# PCB_3U_RJ45.net
KiCad netlist of a schematic drawn in Altium Designer
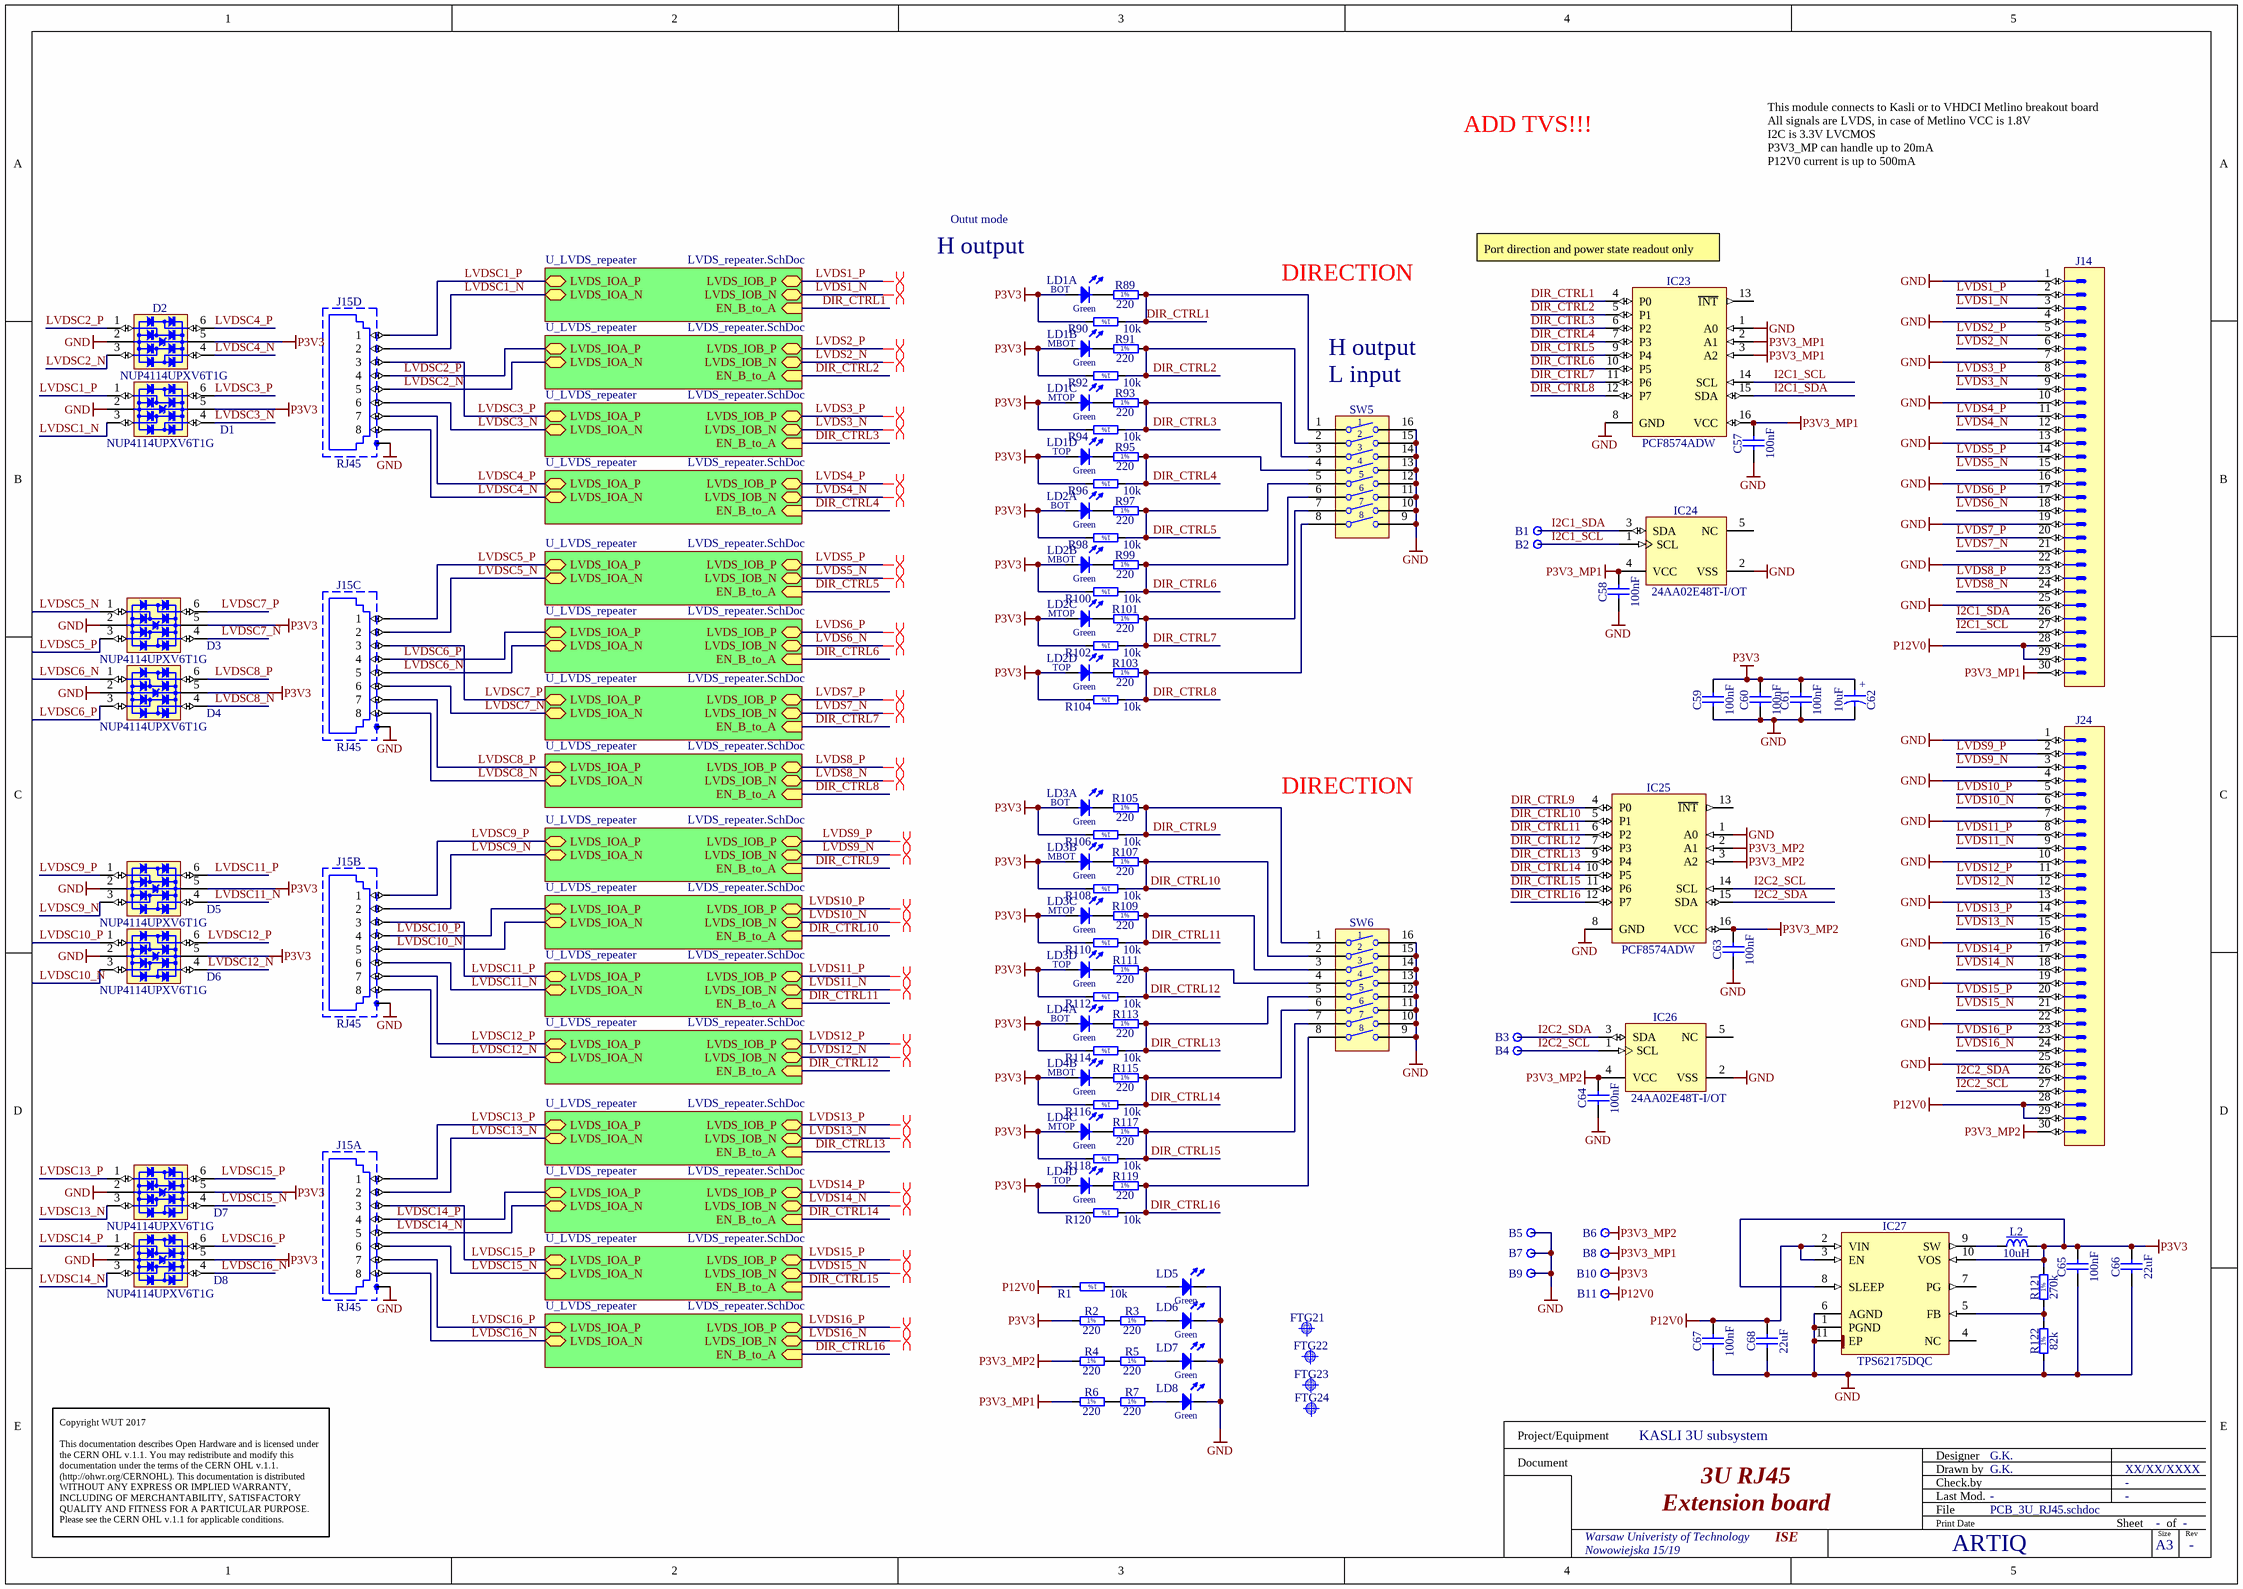
[diagram p0: PCB_3U_RJ45.schdoc]

(export (version "E")
  (design (tool "Eeschema 10.0.6"))
  (components
    (comp (ref "B1")
      (value "Plated Hole")
      (footprint "c130h60")
      (description "Single Terminal Socket")
      (fields (field (name "PART NUMBER") "PLATED_HOLE0.6_PAD1.3") (field (name "AUTHOR") "CERN DEM MR"))
      (libsource (lib "Eletro-mechanical") (part "Single Terminal Socket"))
    )
    (comp (ref "B2")
      (value "Plated Hole")
      (footprint "c130h60")
      (description "Single Terminal Socket")
      (fields (field (name "PART NUMBER") "PLATED_HOLE0.6_PAD1.3") (field (name "AUTHOR") "CERN DEM MR"))
      (libsource (lib "Eletro-mechanical") (part "Single Terminal Socket"))
    )
    (comp (ref "B3")
      (value "Plated Hole")
      (footprint "c130h60")
      (description "Single Terminal Socket")
      (fields (field (name "PART NUMBER") "PLATED_HOLE0.6_PAD1.3") (field (name "AUTHOR") "CERN DEM MR"))
      (libsource (lib "Eletro-mechanical") (part "Single Terminal Socket"))
    )
    (comp (ref "B4")
      (value "Plated Hole")
      (footprint "c130h60")
      (description "Single Terminal Socket")
      (fields (field (name "PART NUMBER") "PLATED_HOLE0.6_PAD1.3") (field (name "AUTHOR") "CERN DEM MR"))
      (libsource (lib "Eletro-mechanical") (part "Single Terminal Socket"))
    )
    (comp (ref "B5")
      (value "Plated Hole")
      (footprint "c130h60")
      (description "Single Terminal Socket")
      (fields (field (name "PART NUMBER") "PLATED_HOLE0.6_PAD1.3") (field (name "AUTHOR") "CERN DEM MR"))
      (libsource (lib "Eletro-mechanical") (part "Single Terminal Socket"))
    )
    (comp (ref "B6")
      (value "Plated Hole")
      (footprint "c130h60")
      (description "Single Terminal Socket")
      (fields (field (name "PART NUMBER") "PLATED_HOLE0.6_PAD1.3") (field (name "AUTHOR") "CERN DEM MR"))
      (libsource (lib "Eletro-mechanical") (part "Single Terminal Socket"))
    )
    (comp (ref "B7")
      (value "Plated Hole")
      (footprint "c130h60")
      (description "Single Terminal Socket")
      (fields (field (name "PART NUMBER") "PLATED_HOLE0.6_PAD1.3") (field (name "AUTHOR") "CERN DEM MR"))
      (libsource (lib "Eletro-mechanical") (part "Single Terminal Socket"))
    )
    (comp (ref "B8")
      (value "Plated Hole")
      (footprint "c130h60")
      (description "Single Terminal Socket")
      (fields (field (name "PART NUMBER") "PLATED_HOLE0.6_PAD1.3") (field (name "AUTHOR") "CERN DEM MR"))
      (libsource (lib "Eletro-mechanical") (part "Single Terminal Socket"))
    )
    (comp (ref "B9")
      (value "Plated Hole")
      (footprint "c130h60")
      (description "Single Terminal Socket")
      (fields (field (name "PART NUMBER") "PLATED_HOLE0.6_PAD1.3") (field (name "AUTHOR") "CERN DEM MR"))
      (libsource (lib "Eletro-mechanical") (part "Single Terminal Socket"))
    )
    (comp (ref "B10")
      (value "Plated Hole")
      (footprint "c130h60")
      (description "Single Terminal Socket")
      (fields (field (name "PART NUMBER") "PLATED_HOLE0.6_PAD1.3") (field (name "AUTHOR") "CERN DEM MR"))
      (libsource (lib "Eletro-mechanical") (part "Single Terminal Socket"))
    )
    (comp (ref "B11")
      (value "Plated Hole")
      (footprint "c130h60")
      (description "Single Terminal Socket")
      (fields (field (name "PART NUMBER") "PLATED_HOLE0.6_PAD1.3") (field (name "AUTHOR") "CERN DEM MR"))
      (libsource (lib "Eletro-mechanical") (part "Single Terminal Socket"))
    )
    (comp (ref "C57")
      (value "100nF")
      (footprint "CAPC1005X55N")
      (description "Non-polarised capacitor")
      (fields
        (field (name "PART NUMBER") "CC0402_100NF_16V_10%_X5R")
        (field (name "VOLTAGE") "16V")
        (field (name "AUTHOR") "CERN DEM JLC")
      )
      (libsource (lib "Capacitors") (part "Capacitor - non polarized"))
    )
    (comp (ref "C58")
      (value "100nF")
      (footprint "CAPC1005X55N")
      (description "Non-polarised capacitor")
      (fields
        (field (name "PART NUMBER") "CC0402_100NF_16V_10%_X5R")
        (field (name "VOLTAGE") "16V")
        (field (name "AUTHOR") "CERN DEM JLC")
      )
      (libsource (lib "Capacitors") (part "Capacitor - non polarized"))
    )
    (comp (ref "C59")
      (value "100nF")
      (footprint "CAPC1005X55N")
      (description "Non-polarised capacitor")
      (fields
        (field (name "PART NUMBER") "CC0402_100NF_16V_10%_X5R")
        (field (name "VOLTAGE") "16V")
        (field (name "AUTHOR") "CERN DEM JLC")
      )
      (libsource (lib "Capacitors") (part "Capacitor - non polarized"))
    )
    (comp (ref "C60")
      (value "100nF")
      (footprint "CAPC1005X55N")
      (description "Non-polarised capacitor")
      (fields
        (field (name "PART NUMBER") "CC0402_100NF_16V_10%_X5R")
        (field (name "VOLTAGE") "16V")
        (field (name "AUTHOR") "CERN DEM JLC")
      )
      (libsource (lib "Capacitors") (part "Capacitor - non polarized"))
    )
    (comp (ref "C61")
      (value "100nF")
      (footprint "CAPC1005X55N")
      (description "Non-polarised capacitor")
      (fields
        (field (name "PART NUMBER") "CC0402_100NF_16V_10%_X5R")
        (field (name "VOLTAGE") "16V")
        (field (name "AUTHOR") "CERN DEM JLC")
      )
      (libsource (lib "Capacitors") (part "Capacitor - non polarized"))
    )
    (comp (ref "C62")
      (value "10uF")
      (footprint "CAPAE430X540N")
      (description "Polarised capacitor")
      (fields
        (field (name "PART NUMBER") "CAE430-540_10UF_16V_20%")
        (field (name "VOLTAGE") "16V")
        (field (name "AUTHOR") "CERN DEM JLC")
      )
      (libsource (lib "Capacitors") (part "Capacitor - polarized"))
    )
    (comp (ref "C63")
      (value "100nF")
      (footprint "CAPC1005X55N")
      (description "Non-polarised capacitor")
      (fields
        (field (name "PART NUMBER") "CC0402_100NF_16V_10%_X5R")
        (field (name "VOLTAGE") "16V")
        (field (name "AUTHOR") "CERN DEM JLC")
      )
      (libsource (lib "Capacitors") (part "Capacitor - non polarized"))
    )
    (comp (ref "C64")
      (value "100nF")
      (footprint "CAPC1005X55N")
      (description "Non-polarised capacitor")
      (fields
        (field (name "PART NUMBER") "CC0402_100NF_16V_10%_X5R")
        (field (name "VOLTAGE") "16V")
        (field (name "AUTHOR") "CERN DEM JLC")
      )
      (libsource (lib "Capacitors") (part "Capacitor - non polarized"))
    )
    (comp (ref "C65")
      (value "100nF")
      (footprint "CAPC1005X55N")
      (description "Non-polarised capacitor")
      (fields
        (field (name "PART NUMBER") "CC0402_100NF_16V_10%_X5R")
        (field (name "VOLTAGE") "16V")
        (field (name "AUTHOR") "CERN DEM JLC")
      )
      (libsource (lib "Capacitors") (part "Capacitor - non polarized"))
    )
    (comp (ref "C66")
      (value "22uF")
      (footprint "CAPC2012X135N")
      (description "Non-polarised capacitor")
      (fields
        (field (name "PART NUMBER") "CC0805_22UF_16V_10%_X5R")
        (field (name "VOLTAGE") "16V")
        (field (name "AUTHOR") "CERN DEM JLC")
      )
      (libsource (lib "Capacitors") (part "Capacitor - non polarized"))
    )
    (comp (ref "C67")
      (value "100nF")
      (footprint "CAPC1005X55N")
      (description "Non-polarised capacitor")
      (fields
        (field (name "PART NUMBER") "CC0402_100NF_16V_10%_X5R")
        (field (name "VOLTAGE") "16V")
        (field (name "AUTHOR") "CERN DEM JLC")
      )
      (libsource (lib "Capacitors") (part "Capacitor - non polarized"))
    )
    (comp (ref "C68")
      (value "22uF")
      (footprint "CAPC2012X135N")
      (description "Non-polarised capacitor")
      (fields
        (field (name "PART NUMBER") "CC0805_22UF_16V_10%_X5R")
        (field (name "VOLTAGE") "16V")
        (field (name "AUTHOR") "CERN DEM JLC")
      )
      (libsource (lib "Capacitors") (part "Capacitor - non polarized"))
    )
    (comp (ref "D1")
      (value "NUP4114UPXV6T1G")
      (footprint "SOTFL50P160X60-6N")
      (fields
        (field (name "VOLTAGE") "5.5V")
        (field (name "MANUFACTURER") "ON SEMICONDUCTOR")
        (field (name "AUTHOR") "CERN DEM JLC")
      )
      (libsource (lib "ICs And Semiconductors") (part "NUP4114"))
    )
    (comp (ref "D2")
      (value "NUP4114UPXV6T1G")
      (footprint "SOTFL50P160X60-6N")
      (fields
        (field (name "VOLTAGE") "5.5V")
        (field (name "MANUFACTURER") "ON SEMICONDUCTOR")
        (field (name "AUTHOR") "CERN DEM JLC")
      )
      (libsource (lib "ICs And Semiconductors") (part "NUP4114"))
    )
    (comp (ref "D3")
      (value "NUP4114UPXV6T1G")
      (footprint "SOTFL50P160X60-6N")
      (fields
        (field (name "VOLTAGE") "5.5V")
        (field (name "MANUFACTURER") "ON SEMICONDUCTOR")
        (field (name "AUTHOR") "CERN DEM JLC")
      )
      (libsource (lib "ICs And Semiconductors") (part "NUP4114"))
    )
    (comp (ref "D4")
      (value "NUP4114UPXV6T1G")
      (footprint "SOTFL50P160X60-6N")
      (fields
        (field (name "VOLTAGE") "5.5V")
        (field (name "MANUFACTURER") "ON SEMICONDUCTOR")
        (field (name "AUTHOR") "CERN DEM JLC")
      )
      (libsource (lib "ICs And Semiconductors") (part "NUP4114"))
    )
    (comp (ref "D5")
      (value "NUP4114UPXV6T1G")
      (footprint "SOTFL50P160X60-6N")
      (fields
        (field (name "VOLTAGE") "5.5V")
        (field (name "MANUFACTURER") "ON SEMICONDUCTOR")
        (field (name "AUTHOR") "CERN DEM JLC")
      )
      (libsource (lib "ICs And Semiconductors") (part "NUP4114"))
    )
    (comp (ref "D6")
      (value "NUP4114UPXV6T1G")
      (footprint "SOTFL50P160X60-6N")
      (fields
        (field (name "VOLTAGE") "5.5V")
        (field (name "MANUFACTURER") "ON SEMICONDUCTOR")
        (field (name "AUTHOR") "CERN DEM JLC")
      )
      (libsource (lib "ICs And Semiconductors") (part "NUP4114"))
    )
    (comp (ref "D7")
      (value "NUP4114UPXV6T1G")
      (footprint "SOTFL50P160X60-6N")
      (fields
        (field (name "VOLTAGE") "5.5V")
        (field (name "MANUFACTURER") "ON SEMICONDUCTOR")
        (field (name "AUTHOR") "CERN DEM JLC")
      )
      (libsource (lib "ICs And Semiconductors") (part "NUP4114"))
    )
    (comp (ref "D8")
      (value "NUP4114UPXV6T1G")
      (footprint "SOTFL50P160X60-6N")
      (fields
        (field (name "VOLTAGE") "5.5V")
        (field (name "MANUFACTURER") "ON SEMICONDUCTOR")
        (field (name "AUTHOR") "CERN DEM JLC")
      )
      (libsource (lib "ICs And Semiconductors") (part "NUP4114"))
    )
    (comp (ref "FTG21")
      (value "Use only in PCB")
      (footprint "FIDUCIAL_TOP_C100-200")
      (description "Fiducial Target")
      (fields (field (name "PART NUMBER") "FIDUCIAL_TARGET_C100-200") (field (name "AUTHOR") "CERN DEM JLC"))
      (libsource (lib "Eletro-mechanical") (part "Fiducial Target"))
    )
    (comp (ref "FTG22")
      (value "Use only in PCB")
      (footprint "FIDUCIAL_TOP_S100-200")
      (description "Fiducial Target")
      (fields (field (name "PART NUMBER") "FIDUCIAL_TARGET_S100-200") (field (name "AUTHOR") "CERN DEM JLC"))
      (libsource (lib "Eletro-mechanical") (part "Fiducial Target"))
    )
    (comp (ref "FTG23")
      (value "Use only in PCB")
      (footprint "FIDUCIAL_TOP_S200-400")
      (description "Fiducial Target")
      (fields (field (name "PART NUMBER") "FIDUCIAL_TARGET_S200-400") (field (name "AUTHOR") "CERN DEM JLC"))
      (libsource (lib "Eletro-mechanical") (part "Fiducial Target"))
    )
    (comp (ref "FTG24")
      (value "Use only in PCB")
      (footprint "FIDUCIAL_TOP_S100-200")
      (description "Fiducial Target")
      (fields (field (name "PART NUMBER") "FIDUCIAL_TARGET_S100-200") (field (name "AUTHOR") "CERN DEM JLC"))
      (libsource (lib "Eletro-mechanical") (part "Fiducial Target"))
    )
    (comp (ref "IC23")
      (value "PCF8574ADW")
      (footprint "SOIC127P1030X265-16N")
      (description "Remote 8-bit I/O Expander For I2C Bus")
      (fields (field (name "MANUFACTURER") "TEXAS INSTRUMENTS") (field (name "AUTHOR") "CERN DEM JLC"))
      (libsource (lib "ICs And Semiconductors") (part "PCF8574ADW"))
    )
    (comp (ref "IC24")
      (value "24AA02E48T-I/OT")
      (footprint "SOT95P280X145-5N")
      (description "1.7V-5.5V, 2K I2C Serial EEPROM With EUI-48 Node Identity")
      (fields (field (name "MANUFACTURER") "MICROCHIP TECHNOLOGY") (field (name "AUTHOR") "CERN DEM MR"))
      (libsource (lib "ICs And Semiconductors") (part "24AA02E48T-I/OT"))
    )
    (comp (ref "IC25")
      (value "PCF8574ADW")
      (footprint "SOIC127P1030X265-16N")
      (description "Remote 8-bit I/O Expander For I2C Bus")
      (fields (field (name "MANUFACTURER") "TEXAS INSTRUMENTS") (field (name "AUTHOR") "CERN DEM JLC"))
      (libsource (lib "ICs And Semiconductors") (part "PCF8574ADW"))
    )
    (comp (ref "IC26")
      (value "24AA02E48T-I/OT")
      (footprint "SOT95P280X145-5N")
      (description "1.7V-5.5V, 2K I2C Serial EEPROM With EUI-48 Node Identity")
      (fields (field (name "MANUFACTURER") "MICROCHIP TECHNOLOGY") (field (name "AUTHOR") "CERN DEM MR"))
      (libsource (lib "ICs And Semiconductors") (part "24AA02E48T-I/OT"))
    )
    (comp (ref "IC27")
      (value "TPS62175DQC")
      (footprint "SON50P200X300X80-11N-R94X250")
      (description "4.75-28VDC to 1-6VDC, 500mA Step-Down Converter With Sleep Mode")
      (fields (field (name "MANUFACTURER") "TEXAS INSTRUMENTS") (field (name "AUTHOR") "CERN DEM JMW"))
      (libsource (lib "ICs And Semiconductors") (part "TPS62175"))
    )
    (comp (ref "J14")
      (value "~")
      (footprint "3M_N2530-6002RB")
      (description "Connector 30 Male")
      (fields
        (field (name "PART NUMBER") "3M_N2530-6002RB")
        (field (name "MANUFACTURER") "3M")
        (field (name "AUTHOR") "CERN DEM JLC")
      )
      (libsource (lib "Connectors") (part "Connector 30 Male"))
    )
    (comp (ref "J15")
      (value "RJ45")
      (footprint "TYCO_5406203-3")
      (description "Connector 4 x RJ45 + Shield")
      (fields
        (field (name "PART NUMBER") "TYCO_5406203-3")
        (field (name "MANUFACTURER") "TYCO ELECTRONICS")
        (field (name "AUTHOR") "CERN DEM JLC")
      )
      (libsource (lib "Connectors") (part "Connector 4 x RJ45 + Shield"))
    )
    (comp (ref "J24")
      (value "~")
      (footprint "3M_N2530-6002RB")
      (description "Connector 30 Male")
      (fields
        (field (name "PART NUMBER") "3M_N2530-6002RB")
        (field (name "MANUFACTURER") "3M")
        (field (name "AUTHOR") "CERN DEM JLC")
      )
      (libsource (lib "Connectors") (part "Connector 30 Male"))
    )
    (comp (ref "L2")
      (value "10uH")
      (footprint "IND_MURATA-PS_8400")
      (description "Inductor With Core")
      (fields
        (field (name "PART NUMBER") "IND_10UH_10%_MURATA-PS_8400")
        (field (name "POWER") "950mA")
        (field (name "AUTHOR") "CERN DEM JLC")
      )
      (libsource (lib "Inductors & Transformers") (part "Inductor With Magnetic core"))
    )
    (comp (ref "LD1")
      (value "Green")
      (footprint "LED_BIVAR_H485CGDL")
      (description "LED x4 Green 1C2A-BOT_3C4A_5C6A_7C8A-TOP")
      (fields
        (field (name "PART NUMBER") "LED_BIVAR_H485CGDL")
        (field (name "MANUFACTURER") "BIVAR")
        (field (name "AUTHOR") "CERN DEM JLC")
      )
      (libsource (lib "ICs And Semiconductors") (part "LED x4 Green 1C2A-BOT_3C4A_5C6A_7C8A-TOP"))
    )
    (comp (ref "LD2")
      (value "Green")
      (footprint "LED_BIVAR_H485CGDL")
      (description "LED x4 Green 1C2A-BOT_3C4A_5C6A_7C8A-TOP")
      (fields
        (field (name "PART NUMBER") "LED_BIVAR_H485CGDL")
        (field (name "MANUFACTURER") "BIVAR")
        (field (name "AUTHOR") "CERN DEM JLC")
      )
      (libsource (lib "ICs And Semiconductors") (part "LED x4 Green 1C2A-BOT_3C4A_5C6A_7C8A-TOP"))
    )
    (comp (ref "LD3")
      (value "Green")
      (footprint "LED_BIVAR_H485CGDL")
      (description "LED x4 Green 1C2A-BOT_3C4A_5C6A_7C8A-TOP")
      (fields
        (field (name "PART NUMBER") "LED_BIVAR_H485CGDL")
        (field (name "MANUFACTURER") "BIVAR")
        (field (name "AUTHOR") "CERN DEM JLC")
      )
      (libsource (lib "ICs And Semiconductors") (part "LED x4 Green 1C2A-BOT_3C4A_5C6A_7C8A-TOP"))
    )
    (comp (ref "LD4")
      (value "Green")
      (footprint "LED_BIVAR_H485CGDL")
      (description "LED x4 Green 1C2A-BOT_3C4A_5C6A_7C8A-TOP")
      (fields
        (field (name "PART NUMBER") "LED_BIVAR_H485CGDL")
        (field (name "MANUFACTURER") "BIVAR")
        (field (name "AUTHOR") "CERN DEM JLC")
      )
      (libsource (lib "ICs And Semiconductors") (part "LED x4 Green 1C2A-BOT_3C4A_5C6A_7C8A-TOP"))
    )
    (comp (ref "LD5")
      (value "Green")
      (footprint "LED_KINGBRIGHT_KPH-1608CGCK")
      (description "LED Green 1C 2A")
      (fields
        (field (name "PART NUMBER") "LED_KINGBRIGHT_KPH-1608CGCK")
        (field (name "MANUFACTURER") "KINGBRIGHT")
        (field (name "AUTHOR") "CERN DEM JLC")
      )
      (libsource (lib "ICs And Semiconductors") (part "LED Green 1C 2A"))
    )
    (comp (ref "LD6")
      (value "Green")
      (footprint "LED_KINGBRIGHT_KPH-1608CGCK")
      (description "LED Green 1C 2A")
      (fields
        (field (name "PART NUMBER") "LED_KINGBRIGHT_KPH-1608CGCK")
        (field (name "MANUFACTURER") "KINGBRIGHT")
        (field (name "AUTHOR") "CERN DEM JLC")
      )
      (libsource (lib "ICs And Semiconductors") (part "LED Green 1C 2A"))
    )
    (comp (ref "LD7")
      (value "Green")
      (footprint "LED_KINGBRIGHT_KPH-1608CGCK")
      (description "LED Green 1C 2A")
      (fields
        (field (name "PART NUMBER") "LED_KINGBRIGHT_KPH-1608CGCK")
        (field (name "MANUFACTURER") "KINGBRIGHT")
        (field (name "AUTHOR") "CERN DEM JLC")
      )
      (libsource (lib "ICs And Semiconductors") (part "LED Green 1C 2A"))
    )
    (comp (ref "LD8")
      (value "Green")
      (footprint "LED_KINGBRIGHT_KPH-1608CGCK")
      (description "LED Green 1C 2A")
      (fields
        (field (name "PART NUMBER") "LED_KINGBRIGHT_KPH-1608CGCK")
        (field (name "MANUFACTURER") "KINGBRIGHT")
        (field (name "AUTHOR") "CERN DEM JLC")
      )
      (libsource (lib "ICs And Semiconductors") (part "LED Green 1C 2A"))
    )
    (comp (ref "R1")
      (value "10k")
      (footprint "RESC1005X40N")
      (description "Resistor - 1%")
      (fields
        (field (name "PART NUMBER") "R0402_10K_1%_0.0625W_100PPM")
        (field (name "POWER") "0.0625W")
        (field (name "AUTHOR") "CERN DEM JLC")
      )
      (libsource (lib "Resistors") (part "Resistor - 1%"))
    )
    (comp (ref "R2")
      (value "220")
      (footprint "RESC1608X55N")
      (description "Resistor - 1%")
      (fields
        (field (name "PART NUMBER") "R0603_220R_1%_0.1W_100PPM")
        (field (name "POWER") "0.1W")
        (field (name "AUTHOR") "CERN DEM JLC")
      )
      (libsource (lib "Resistors") (part "Resistor - 1%"))
    )
    (comp (ref "R3")
      (value "220")
      (footprint "RESC1608X55N")
      (description "Resistor - 1%")
      (fields
        (field (name "PART NUMBER") "R0603_220R_1%_0.1W_100PPM")
        (field (name "POWER") "0.1W")
        (field (name "AUTHOR") "CERN DEM JLC")
      )
      (libsource (lib "Resistors") (part "Resistor - 1%"))
    )
    (comp (ref "R4")
      (value "220")
      (footprint "RESC1608X55N")
      (description "Resistor - 1%")
      (fields
        (field (name "PART NUMBER") "R0603_220R_1%_0.1W_100PPM")
        (field (name "POWER") "0.1W")
        (field (name "AUTHOR") "CERN DEM JLC")
      )
      (libsource (lib "Resistors") (part "Resistor - 1%"))
    )
    (comp (ref "R5")
      (value "220")
      (footprint "RESC1608X55N")
      (description "Resistor - 1%")
      (fields
        (field (name "PART NUMBER") "R0603_220R_1%_0.1W_100PPM")
        (field (name "POWER") "0.1W")
        (field (name "AUTHOR") "CERN DEM JLC")
      )
      (libsource (lib "Resistors") (part "Resistor - 1%"))
    )
    (comp (ref "R6")
      (value "220")
      (footprint "RESC1608X55N")
      (description "Resistor - 1%")
      (fields
        (field (name "PART NUMBER") "R0603_220R_1%_0.1W_100PPM")
        (field (name "POWER") "0.1W")
        (field (name "AUTHOR") "CERN DEM JLC")
      )
      (libsource (lib "Resistors") (part "Resistor - 1%"))
    )
    (comp (ref "R7")
      (value "220")
      (footprint "RESC1608X55N")
      (description "Resistor - 1%")
      (fields
        (field (name "PART NUMBER") "R0603_220R_1%_0.1W_100PPM")
        (field (name "POWER") "0.1W")
        (field (name "AUTHOR") "CERN DEM JLC")
      )
      (libsource (lib "Resistors") (part "Resistor - 1%"))
    )
    (comp (ref "R89")
      (value "220")
      (footprint "RESC1608X55N")
      (description "Resistor - 1%")
      (fields
        (field (name "PART NUMBER") "R0603_220R_1%_0.1W_100PPM")
        (field (name "POWER") "0.1W")
        (field (name "AUTHOR") "CERN DEM JLC")
      )
      (libsource (lib "Resistors") (part "Resistor - 1%"))
    )
    (comp (ref "R90")
      (value "10k")
      (footprint "RESC1005X40N")
      (description "Resistor - 1%")
      (fields
        (field (name "PART NUMBER") "R0402_10K_1%_0.0625W_100PPM")
        (field (name "POWER") "0.0625W")
        (field (name "AUTHOR") "CERN DEM JLC")
      )
      (libsource (lib "Resistors") (part "Resistor - 1%"))
    )
    (comp (ref "R91")
      (value "220")
      (footprint "RESC1608X55N")
      (description "Resistor - 1%")
      (fields
        (field (name "PART NUMBER") "R0603_220R_1%_0.1W_100PPM")
        (field (name "POWER") "0.1W")
        (field (name "AUTHOR") "CERN DEM JLC")
      )
      (libsource (lib "Resistors") (part "Resistor - 1%"))
    )
    (comp (ref "R92")
      (value "10k")
      (footprint "RESC1005X40N")
      (description "Resistor - 1%")
      (fields
        (field (name "PART NUMBER") "R0402_10K_1%_0.0625W_100PPM")
        (field (name "POWER") "0.0625W")
        (field (name "AUTHOR") "CERN DEM JLC")
      )
      (libsource (lib "Resistors") (part "Resistor - 1%"))
    )
    (comp (ref "R93")
      (value "220")
      (footprint "RESC1608X55N")
      (description "Resistor - 1%")
      (fields
        (field (name "PART NUMBER") "R0603_220R_1%_0.1W_100PPM")
        (field (name "POWER") "0.1W")
        (field (name "AUTHOR") "CERN DEM JLC")
      )
      (libsource (lib "Resistors") (part "Resistor - 1%"))
    )
    (comp (ref "R94")
      (value "10k")
      (footprint "RESC1005X40N")
      (description "Resistor - 1%")
      (fields
        (field (name "PART NUMBER") "R0402_10K_1%_0.0625W_100PPM")
        (field (name "POWER") "0.0625W")
        (field (name "AUTHOR") "CERN DEM JLC")
      )
      (libsource (lib "Resistors") (part "Resistor - 1%"))
    )
    (comp (ref "R95")
      (value "220")
      (footprint "RESC1608X55N")
      (description "Resistor - 1%")
      (fields
        (field (name "PART NUMBER") "R0603_220R_1%_0.1W_100PPM")
        (field (name "POWER") "0.1W")
        (field (name "AUTHOR") "CERN DEM JLC")
      )
      (libsource (lib "Resistors") (part "Resistor - 1%"))
    )
    (comp (ref "R96")
      (value "10k")
      (footprint "RESC1005X40N")
      (description "Resistor - 1%")
      (fields
        (field (name "PART NUMBER") "R0402_10K_1%_0.0625W_100PPM")
        (field (name "POWER") "0.0625W")
        (field (name "AUTHOR") "CERN DEM JLC")
      )
      (libsource (lib "Resistors") (part "Resistor - 1%"))
    )
    (comp (ref "R97")
      (value "220")
      (footprint "RESC1608X55N")
      (description "Resistor - 1%")
      (fields
        (field (name "PART NUMBER") "R0603_220R_1%_0.1W_100PPM")
        (field (name "POWER") "0.1W")
        (field (name "AUTHOR") "CERN DEM JLC")
      )
      (libsource (lib "Resistors") (part "Resistor - 1%"))
    )
    (comp (ref "R98")
      (value "10k")
      (footprint "RESC1005X40N")
      (description "Resistor - 1%")
      (fields
        (field (name "PART NUMBER") "R0402_10K_1%_0.0625W_100PPM")
        (field (name "POWER") "0.0625W")
        (field (name "AUTHOR") "CERN DEM JLC")
      )
      (libsource (lib "Resistors") (part "Resistor - 1%"))
    )
    (comp (ref "R99")
      (value "220")
      (footprint "RESC1608X55N")
      (description "Resistor - 1%")
      (fields
        (field (name "PART NUMBER") "R0603_220R_1%_0.1W_100PPM")
        (field (name "POWER") "0.1W")
        (field (name "AUTHOR") "CERN DEM JLC")
      )
      (libsource (lib "Resistors") (part "Resistor - 1%"))
    )
    (comp (ref "R100")
      (value "10k")
      (footprint "RESC1005X40N")
      (description "Resistor - 1%")
      (fields
        (field (name "PART NUMBER") "R0402_10K_1%_0.0625W_100PPM")
        (field (name "POWER") "0.0625W")
        (field (name "AUTHOR") "CERN DEM JLC")
      )
      (libsource (lib "Resistors") (part "Resistor - 1%"))
    )
    (comp (ref "R101")
      (value "220")
      (footprint "RESC1608X55N")
      (description "Resistor - 1%")
      (fields
        (field (name "PART NUMBER") "R0603_220R_1%_0.1W_100PPM")
        (field (name "POWER") "0.1W")
        (field (name "AUTHOR") "CERN DEM JLC")
      )
      (libsource (lib "Resistors") (part "Resistor - 1%"))
    )
    (comp (ref "R102")
      (value "10k")
      (footprint "RESC1005X40N")
      (description "Resistor - 1%")
      (fields
        (field (name "PART NUMBER") "R0402_10K_1%_0.0625W_100PPM")
        (field (name "POWER") "0.0625W")
        (field (name "AUTHOR") "CERN DEM JLC")
      )
      (libsource (lib "Resistors") (part "Resistor - 1%"))
    )
    (comp (ref "R103")
      (value "220")
      (footprint "RESC1608X55N")
      (description "Resistor - 1%")
      (fields
        (field (name "PART NUMBER") "R0603_220R_1%_0.1W_100PPM")
        (field (name "POWER") "0.1W")
        (field (name "AUTHOR") "CERN DEM JLC")
      )
      (libsource (lib "Resistors") (part "Resistor - 1%"))
    )
    (comp (ref "R104")
      (value "10k")
      (footprint "RESC1005X40N")
      (description "Resistor - 1%")
      (fields
        (field (name "PART NUMBER") "R0402_10K_1%_0.0625W_100PPM")
        (field (name "POWER") "0.0625W")
        (field (name "AUTHOR") "CERN DEM JLC")
      )
      (libsource (lib "Resistors") (part "Resistor - 1%"))
    )
    (comp (ref "R105")
      (value "220")
      (footprint "RESC1608X55N")
      (description "Resistor - 1%")
      (fields
        (field (name "PART NUMBER") "R0603_220R_1%_0.1W_100PPM")
        (field (name "POWER") "0.1W")
        (field (name "AUTHOR") "CERN DEM JLC")
      )
      (libsource (lib "Resistors") (part "Resistor - 1%"))
    )
    (comp (ref "R106")
      (value "10k")
      (footprint "RESC1005X40N")
      (description "Resistor - 1%")
      (fields
        (field (name "PART NUMBER") "R0402_10K_1%_0.0625W_100PPM")
        (field (name "POWER") "0.0625W")
        (field (name "AUTHOR") "CERN DEM JLC")
      )
      (libsource (lib "Resistors") (part "Resistor - 1%"))
    )
    (comp (ref "R107")
      (value "220")
      (footprint "RESC1608X55N")
      (description "Resistor - 1%")
      (fields
        (field (name "PART NUMBER") "R0603_220R_1%_0.1W_100PPM")
        (field (name "POWER") "0.1W")
        (field (name "AUTHOR") "CERN DEM JLC")
      )
      (libsource (lib "Resistors") (part "Resistor - 1%"))
    )
    (comp (ref "R108")
      (value "10k")
      (footprint "RESC1005X40N")
      (description "Resistor - 1%")
      (fields
        (field (name "PART NUMBER") "R0402_10K_1%_0.0625W_100PPM")
        (field (name "POWER") "0.0625W")
        (field (name "AUTHOR") "CERN DEM JLC")
      )
      (libsource (lib "Resistors") (part "Resistor - 1%"))
    )
    (comp (ref "R109")
      (value "220")
      (footprint "RESC1608X55N")
      (description "Resistor - 1%")
      (fields
        (field (name "PART NUMBER") "R0603_220R_1%_0.1W_100PPM")
        (field (name "POWER") "0.1W")
        (field (name "AUTHOR") "CERN DEM JLC")
      )
      (libsource (lib "Resistors") (part "Resistor - 1%"))
    )
    (comp (ref "R110")
      (value "10k")
      (footprint "RESC1005X40N")
      (description "Resistor - 1%")
      (fields
        (field (name "PART NUMBER") "R0402_10K_1%_0.0625W_100PPM")
        (field (name "POWER") "0.0625W")
        (field (name "AUTHOR") "CERN DEM JLC")
      )
      (libsource (lib "Resistors") (part "Resistor - 1%"))
    )
    (comp (ref "R111")
      (value "220")
      (footprint "RESC1608X55N")
      (description "Resistor - 1%")
      (fields
        (field (name "PART NUMBER") "R0603_220R_1%_0.1W_100PPM")
        (field (name "POWER") "0.1W")
        (field (name "AUTHOR") "CERN DEM JLC")
      )
      (libsource (lib "Resistors") (part "Resistor - 1%"))
    )
    (comp (ref "R112")
      (value "10k")
      (footprint "RESC1005X40N")
      (description "Resistor - 1%")
      (fields
        (field (name "PART NUMBER") "R0402_10K_1%_0.0625W_100PPM")
        (field (name "POWER") "0.0625W")
        (field (name "AUTHOR") "CERN DEM JLC")
      )
      (libsource (lib "Resistors") (part "Resistor - 1%"))
    )
    (comp (ref "R113")
      (value "220")
      (footprint "RESC1608X55N")
      (description "Resistor - 1%")
      (fields
        (field (name "PART NUMBER") "R0603_220R_1%_0.1W_100PPM")
        (field (name "POWER") "0.1W")
        (field (name "AUTHOR") "CERN DEM JLC")
      )
      (libsource (lib "Resistors") (part "Resistor - 1%"))
    )
    (comp (ref "R114")
      (value "10k")
      (footprint "RESC1005X40N")
      (description "Resistor - 1%")
      (fields
        (field (name "PART NUMBER") "R0402_10K_1%_0.0625W_100PPM")
        (field (name "POWER") "0.0625W")
        (field (name "AUTHOR") "CERN DEM JLC")
      )
      (libsource (lib "Resistors") (part "Resistor - 1%"))
    )
    (comp (ref "R115")
      (value "220")
      (footprint "RESC1608X55N")
      (description "Resistor - 1%")
      (fields
        (field (name "PART NUMBER") "R0603_220R_1%_0.1W_100PPM")
        (field (name "POWER") "0.1W")
        (field (name "AUTHOR") "CERN DEM JLC")
      )
      (libsource (lib "Resistors") (part "Resistor - 1%"))
    )
    (comp (ref "R116")
      (value "10k")
      (footprint "RESC1005X40N")
      (description "Resistor - 1%")
      (fields
        (field (name "PART NUMBER") "R0402_10K_1%_0.0625W_100PPM")
        (field (name "POWER") "0.0625W")
        (field (name "AUTHOR") "CERN DEM JLC")
      )
      (libsource (lib "Resistors") (part "Resistor - 1%"))
    )
    (comp (ref "R117")
      (value "220")
      (footprint "RESC1608X55N")
      (description "Resistor - 1%")
      (fields
        (field (name "PART NUMBER") "R0603_220R_1%_0.1W_100PPM")
        (field (name "POWER") "0.1W")
        (field (name "AUTHOR") "CERN DEM JLC")
      )
      (libsource (lib "Resistors") (part "Resistor - 1%"))
    )
    (comp (ref "R118")
      (value "10k")
      (footprint "RESC1005X40N")
      (description "Resistor - 1%")
      (fields
        (field (name "PART NUMBER") "R0402_10K_1%_0.0625W_100PPM")
        (field (name "POWER") "0.0625W")
        (field (name "AUTHOR") "CERN DEM JLC")
      )
      (libsource (lib "Resistors") (part "Resistor - 1%"))
    )
    (comp (ref "R119")
      (value "220")
      (footprint "RESC1608X55N")
      (description "Resistor - 1%")
      (fields
        (field (name "PART NUMBER") "R0603_220R_1%_0.1W_100PPM")
        (field (name "POWER") "0.1W")
        (field (name "AUTHOR") "CERN DEM JLC")
      )
      (libsource (lib "Resistors") (part "Resistor - 1%"))
    )
    (comp (ref "R120")
      (value "10k")
      (footprint "RESC1005X40N")
      (description "Resistor - 1%")
      (fields
        (field (name "PART NUMBER") "R0402_10K_1%_0.0625W_100PPM")
        (field (name "POWER") "0.0625W")
        (field (name "AUTHOR") "CERN DEM JLC")
      )
      (libsource (lib "Resistors") (part "Resistor - 1%"))
    )
    (comp (ref "R121")
      (value "270k")
      (footprint "RESC1608X55N")
      (description "Resistor - 1%")
      (fields
        (field (name "PART NUMBER") "R0603_270K_1%_0.1W_100PPM")
        (field (name "POWER") "0.1W")
        (field (name "AUTHOR") "CERN DEM JLC")
      )
      (libsource (lib "Resistors") (part "Resistor - 1%"))
    )
    (comp (ref "R122")
      (value "82k")
      (footprint "RESC1608X55N")
      (description "Resistor - 1%")
      (fields
        (field (name "PART NUMBER") "R0603_82K_1%_0.1W_100PPM")
        (field (name "POWER") "0.1W")
        (field (name "AUTHOR") "CERN DEM JLC")
      )
      (libsource (lib "Resistors") (part "Resistor - 1%"))
    )
    (comp (ref "SW5")
      (value "Switch")
      (footprint "SW_TYCO_1-1571983-0")
      (description "8 Ways SPST DIP Switch")
      (fields
        (field (name "PART NUMBER") "SW_TYCO_1-1571983-0")
        (field (name "MANUFACTURER") "TYCO")
        (field (name "AUTHOR") "CERN DEM JLC")
      )
      (libsource (lib "Eletro-mechanical") (part "SW 8x SPST DIP Switch"))
    )
    (comp (ref "SW6")
      (value "Switch")
      (footprint "SW_TYCO_1-1571983-0")
      (description "8 Ways SPST DIP Switch")
      (fields
        (field (name "PART NUMBER") "SW_TYCO_1-1571983-0")
        (field (name "MANUFACTURER") "TYCO")
        (field (name "AUTHOR") "CERN DEM JLC")
      )
      (libsource (lib "Eletro-mechanical") (part "SW 8x SPST DIP Switch"))
    )
  )
  (nets
    (net (code "1") (name "/DIR_CTRL1") (class "Default")
      (node (ref "IC23") (pin "4") (pinfunction "P0_4") (pintype "bidirectional"))
      (node (ref "R89") (pin "2") (pinfunction "2_2") (pintype "passive"))
      (node (ref "R90") (pin "1") (pinfunction "1_1") (pintype "passive"))
      (node (ref "SW5") (pin "1") (pinfunction "1_1") (pintype "passive"))
    )
    (net (code "2") (name "/DIR_CTRL2") (class "Default")
      (node (ref "IC23") (pin "5") (pinfunction "P1_5") (pintype "bidirectional"))
      (node (ref "R91") (pin "2") (pinfunction "2_2") (pintype "passive"))
      (node (ref "R92") (pin "1") (pinfunction "1_1") (pintype "passive"))
      (node (ref "SW5") (pin "2") (pinfunction "2_2") (pintype "passive"))
    )
    (net (code "3") (name "/DIR_CTRL3") (class "Default")
      (node (ref "IC23") (pin "6") (pinfunction "P2_6") (pintype "bidirectional"))
      (node (ref "R93") (pin "2") (pinfunction "2_2") (pintype "passive"))
      (node (ref "R94") (pin "1") (pinfunction "1_1") (pintype "passive"))
      (node (ref "SW5") (pin "3") (pinfunction "3_3") (pintype "passive"))
    )
    (net (code "4") (name "/DIR_CTRL4") (class "Default")
      (node (ref "IC23") (pin "7") (pinfunction "P3_7") (pintype "bidirectional"))
      (node (ref "R95") (pin "2") (pinfunction "2_2") (pintype "passive"))
      (node (ref "R96") (pin "1") (pinfunction "1_1") (pintype "passive"))
      (node (ref "SW5") (pin "4") (pinfunction "4_4") (pintype "passive"))
    )
    (net (code "5") (name "/DIR_CTRL5") (class "Default")
      (node (ref "IC23") (pin "9") (pinfunction "P4_9") (pintype "bidirectional"))
      (node (ref "R97") (pin "2") (pinfunction "2_2") (pintype "passive"))
      (node (ref "R98") (pin "1") (pinfunction "1_1") (pintype "passive"))
      (node (ref "SW5") (pin "5") (pinfunction "5_5") (pintype "passive"))
    )
    (net (code "6") (name "/DIR_CTRL6") (class "Default")
      (node (ref "IC23") (pin "10") (pinfunction "P5_10") (pintype "bidirectional"))
      (node (ref "R100") (pin "1") (pinfunction "1_1") (pintype "passive"))
      (node (ref "R99") (pin "2") (pinfunction "2_2") (pintype "passive"))
      (node (ref "SW5") (pin "6") (pinfunction "6_6") (pintype "passive"))
    )
    (net (code "7") (name "/DIR_CTRL7") (class "Default")
      (node (ref "IC23") (pin "11") (pinfunction "P6_11") (pintype "bidirectional"))
      (node (ref "R101") (pin "2") (pinfunction "2_2") (pintype "passive"))
      (node (ref "R102") (pin "1") (pinfunction "1_1") (pintype "passive"))
      (node (ref "SW5") (pin "7") (pinfunction "7_7") (pintype "passive"))
    )
    (net (code "8") (name "/DIR_CTRL8") (class "Default")
      (node (ref "IC23") (pin "12") (pinfunction "P7_12") (pintype "bidirectional"))
      (node (ref "R103") (pin "2") (pinfunction "2_2") (pintype "passive"))
      (node (ref "R104") (pin "1") (pinfunction "1_1") (pintype "passive"))
      (node (ref "SW5") (pin "8") (pinfunction "8_8") (pintype "passive"))
    )
    (net (code "9") (name "/DIR_CTRL9") (class "Default")
      (node (ref "IC25") (pin "4") (pinfunction "P0_4") (pintype "bidirectional"))
      (node (ref "R105") (pin "2") (pinfunction "2_2") (pintype "passive"))
      (node (ref "R106") (pin "1") (pinfunction "1_1") (pintype "passive"))
      (node (ref "SW6") (pin "1") (pinfunction "1_1") (pintype "passive"))
    )
    (net (code "10") (name "/DIR_CTRL10") (class "Default")
      (node (ref "IC25") (pin "5") (pinfunction "P1_5") (pintype "bidirectional"))
      (node (ref "R107") (pin "2") (pinfunction "2_2") (pintype "passive"))
      (node (ref "R108") (pin "1") (pinfunction "1_1") (pintype "passive"))
      (node (ref "SW6") (pin "2") (pinfunction "2_2") (pintype "passive"))
    )
    (net (code "11") (name "/DIR_CTRL11") (class "Default")
      (node (ref "IC25") (pin "6") (pinfunction "P2_6") (pintype "bidirectional"))
      (node (ref "R109") (pin "2") (pinfunction "2_2") (pintype "passive"))
      (node (ref "R110") (pin "1") (pinfunction "1_1") (pintype "passive"))
      (node (ref "SW6") (pin "3") (pinfunction "3_3") (pintype "passive"))
    )
    (net (code "12") (name "/DIR_CTRL12") (class "Default")
      (node (ref "IC25") (pin "7") (pinfunction "P3_7") (pintype "bidirectional"))
      (node (ref "R111") (pin "2") (pinfunction "2_2") (pintype "passive"))
      (node (ref "R112") (pin "1") (pinfunction "1_1") (pintype "passive"))
      (node (ref "SW6") (pin "4") (pinfunction "4_4") (pintype "passive"))
    )
    (net (code "13") (name "/DIR_CTRL13") (class "Default")
      (node (ref "IC25") (pin "9") (pinfunction "P4_9") (pintype "bidirectional"))
      (node (ref "R113") (pin "2") (pinfunction "2_2") (pintype "passive"))
      (node (ref "R114") (pin "1") (pinfunction "1_1") (pintype "passive"))
      (node (ref "SW6") (pin "5") (pinfunction "5_5") (pintype "passive"))
    )
    (net (code "14") (name "/DIR_CTRL14") (class "Default")
      (node (ref "IC25") (pin "10") (pinfunction "P5_10") (pintype "bidirectional"))
      (node (ref "R115") (pin "2") (pinfunction "2_2") (pintype "passive"))
      (node (ref "R116") (pin "1") (pinfunction "1_1") (pintype "passive"))
      (node (ref "SW6") (pin "6") (pinfunction "6_6") (pintype "passive"))
    )
    (net (code "15") (name "/DIR_CTRL15") (class "Default")
      (node (ref "IC25") (pin "11") (pinfunction "P6_11") (pintype "bidirectional"))
      (node (ref "R117") (pin "2") (pinfunction "2_2") (pintype "passive"))
      (node (ref "R118") (pin "1") (pinfunction "1_1") (pintype "passive"))
      (node (ref "SW6") (pin "7") (pinfunction "7_7") (pintype "passive"))
    )
    (net (code "16") (name "/DIR_CTRL16") (class "Default")
      (node (ref "IC25") (pin "12") (pinfunction "P7_12") (pintype "bidirectional"))
      (node (ref "R119") (pin "2") (pinfunction "2_2") (pintype "passive"))
      (node (ref "R120") (pin "1") (pinfunction "1_1") (pintype "passive"))
      (node (ref "SW6") (pin "8") (pinfunction "8_8") (pintype "passive"))
    )
    (net (code "17") (name "/I2C1_SCL") (class "Default")
      (node (ref "B2") (pin "1") (pinfunction "1_1") (pintype "bidirectional"))
      (node (ref "IC23") (pin "14") (pinfunction "SCL_14") (pintype "input"))
      (node (ref "IC24") (pin "1") (pinfunction "SCL_1") (pintype "input"))
      (node (ref "J14") (pin "27") (pinfunction "27_27") (pintype "bidirectional"))
    )
    (net (code "18") (name "/I2C1_SDA") (class "Default")
      (node (ref "B1") (pin "1") (pinfunction "1_1") (pintype "bidirectional"))
      (node (ref "IC23") (pin "15") (pinfunction "SDA_15") (pintype "bidirectional"))
      (node (ref "IC24") (pin "3") (pinfunction "SDA_3") (pintype "bidirectional"))
      (node (ref "J14") (pin "26") (pinfunction "26_26") (pintype "bidirectional"))
    )
    (net (code "19") (name "/I2C2_SCL") (class "Default")
      (node (ref "B4") (pin "1") (pinfunction "1_1") (pintype "bidirectional"))
      (node (ref "IC25") (pin "14") (pinfunction "SCL_14") (pintype "input"))
      (node (ref "IC26") (pin "1") (pinfunction "SCL_1") (pintype "input"))
      (node (ref "J24") (pin "27") (pinfunction "27_27") (pintype "bidirectional"))
    )
    (net (code "20") (name "/I2C2_SDA") (class "Default")
      (node (ref "B3") (pin "1") (pinfunction "1_1") (pintype "bidirectional"))
      (node (ref "IC25") (pin "15") (pinfunction "SDA_15") (pintype "bidirectional"))
      (node (ref "IC26") (pin "3") (pinfunction "SDA_3") (pintype "bidirectional"))
      (node (ref "J24") (pin "26") (pinfunction "26_26") (pintype "bidirectional"))
    )
    (net (code "21") (name "/LVDS1_N") (class "Default")
      (node (ref "J14") (pin "3") (pinfunction "3_3") (pintype "bidirectional"))
    )
    (net (code "22") (name "/LVDS1_P") (class "Default")
      (node (ref "J14") (pin "2") (pinfunction "2_2") (pintype "bidirectional"))
    )
    (net (code "23") (name "/LVDS2_N") (class "Default")
      (node (ref "J14") (pin "6") (pinfunction "6_6") (pintype "bidirectional"))
    )
    (net (code "24") (name "/LVDS2_P") (class "Default")
      (node (ref "J14") (pin "5") (pinfunction "5_5") (pintype "bidirectional"))
    )
    (net (code "25") (name "/LVDS3_N") (class "Default")
      (node (ref "J14") (pin "9") (pinfunction "9_9") (pintype "bidirectional"))
    )
    (net (code "26") (name "/LVDS3_P") (class "Default")
      (node (ref "J14") (pin "8") (pinfunction "8_8") (pintype "bidirectional"))
    )
    (net (code "27") (name "/LVDS4_N") (class "Default")
      (node (ref "J14") (pin "12") (pinfunction "12_12") (pintype "bidirectional"))
    )
    (net (code "28") (name "/LVDS4_P") (class "Default")
      (node (ref "J14") (pin "11") (pinfunction "11_11") (pintype "bidirectional"))
    )
    (net (code "29") (name "/LVDS5_N") (class "Default")
      (node (ref "J14") (pin "15") (pinfunction "15_15") (pintype "bidirectional"))
    )
    (net (code "30") (name "/LVDS5_P") (class "Default")
      (node (ref "J14") (pin "14") (pinfunction "14_14") (pintype "bidirectional"))
    )
    (net (code "31") (name "/LVDS6_N") (class "Default")
      (node (ref "J14") (pin "18") (pinfunction "18_18") (pintype "bidirectional"))
    )
    (net (code "32") (name "/LVDS6_P") (class "Default")
      (node (ref "J14") (pin "17") (pinfunction "17_17") (pintype "bidirectional"))
    )
    (net (code "33") (name "/LVDS7_N") (class "Default")
      (node (ref "J14") (pin "21") (pinfunction "21_21") (pintype "bidirectional"))
    )
    (net (code "34") (name "/LVDS7_P") (class "Default")
      (node (ref "J14") (pin "20") (pinfunction "20_20") (pintype "bidirectional"))
    )
    (net (code "35") (name "/LVDS8_N") (class "Default")
      (node (ref "J14") (pin "24") (pinfunction "24_24") (pintype "bidirectional"))
    )
    (net (code "36") (name "/LVDS8_P") (class "Default")
      (node (ref "J14") (pin "23") (pinfunction "23_23") (pintype "bidirectional"))
    )
    (net (code "37") (name "/LVDS9_N") (class "Default")
      (node (ref "J24") (pin "3") (pinfunction "3_3") (pintype "bidirectional"))
    )
    (net (code "38") (name "/LVDS9_P") (class "Default")
      (node (ref "J24") (pin "2") (pinfunction "2_2") (pintype "bidirectional"))
    )
    (net (code "39") (name "/LVDS10_N") (class "Default")
      (node (ref "J24") (pin "6") (pinfunction "6_6") (pintype "bidirectional"))
    )
    (net (code "40") (name "/LVDS10_P") (class "Default")
      (node (ref "J24") (pin "5") (pinfunction "5_5") (pintype "bidirectional"))
    )
    (net (code "41") (name "/LVDS11_N") (class "Default")
      (node (ref "J24") (pin "9") (pinfunction "9_9") (pintype "bidirectional"))
    )
    (net (code "42") (name "/LVDS11_P") (class "Default")
      (node (ref "J24") (pin "8") (pinfunction "8_8") (pintype "bidirectional"))
    )
    (net (code "43") (name "/LVDS12_N") (class "Default")
      (node (ref "J24") (pin "12") (pinfunction "12_12") (pintype "bidirectional"))
    )
    (net (code "44") (name "/LVDS12_P") (class "Default")
      (node (ref "J24") (pin "11") (pinfunction "11_11") (pintype "bidirectional"))
    )
    (net (code "45") (name "/LVDS13_N") (class "Default")
      (node (ref "J24") (pin "15") (pinfunction "15_15") (pintype "bidirectional"))
    )
    (net (code "46") (name "/LVDS13_P") (class "Default")
      (node (ref "J24") (pin "14") (pinfunction "14_14") (pintype "bidirectional"))
    )
    (net (code "47") (name "/LVDS14_N") (class "Default")
      (node (ref "J24") (pin "18") (pinfunction "18_18") (pintype "bidirectional"))
    )
    (net (code "48") (name "/LVDS14_P") (class "Default")
      (node (ref "J24") (pin "17") (pinfunction "17_17") (pintype "bidirectional"))
    )
    (net (code "49") (name "/LVDS15_N") (class "Default")
      (node (ref "J24") (pin "21") (pinfunction "21_21") (pintype "bidirectional"))
    )
    (net (code "50") (name "/LVDS15_P") (class "Default")
      (node (ref "J24") (pin "20") (pinfunction "20_20") (pintype "bidirectional"))
    )
    (net (code "51") (name "/LVDS16_N") (class "Default")
      (node (ref "J24") (pin "24") (pinfunction "24_24") (pintype "bidirectional"))
    )
    (net (code "52") (name "/LVDS16_P") (class "Default")
      (node (ref "J24") (pin "23") (pinfunction "23_23") (pintype "bidirectional"))
    )
    (net (code "53") (name "/LVDSC1_N") (class "Default")
      (node (ref "D1") (pin "3") (pinfunction "I/O2_3") (pintype "bidirectional"))
      (node (ref "J15") (pin "2D") (pinfunction "2_2D") (pintype "bidirectional"))
    )
    (net (code "54") (name "/LVDSC1_P") (class "Default")
      (node (ref "D1") (pin "1") (pinfunction "I/O1_1") (pintype "bidirectional"))
      (node (ref "J15") (pin "1D") (pinfunction "1_1D") (pintype "bidirectional"))
    )
    (net (code "55") (name "/LVDSC2_N") (class "Default")
      (node (ref "D2") (pin "3") (pinfunction "I/O2_3") (pintype "bidirectional"))
      (node (ref "J15") (pin "5D") (pinfunction "5_5D") (pintype "bidirectional"))
    )
    (net (code "56") (name "/LVDSC2_P") (class "Default")
      (node (ref "D2") (pin "1") (pinfunction "I/O1_1") (pintype "bidirectional"))
      (node (ref "J15") (pin "4D") (pinfunction "4_4D") (pintype "bidirectional"))
    )
    (net (code "57") (name "/LVDSC3_N") (class "Default")
      (node (ref "D1") (pin "4") (pinfunction "I/O3_4") (pintype "bidirectional"))
      (node (ref "J15") (pin "6D") (pinfunction "6_6D") (pintype "bidirectional"))
    )
    (net (code "58") (name "/LVDSC3_P") (class "Default")
      (node (ref "D1") (pin "6") (pinfunction "I/O4_6") (pintype "bidirectional"))
      (node (ref "J15") (pin "3D") (pinfunction "3_3D") (pintype "bidirectional"))
    )
    (net (code "59") (name "/LVDSC4_N") (class "Default")
      (node (ref "D2") (pin "4") (pinfunction "I/O3_4") (pintype "bidirectional"))
      (node (ref "J15") (pin "8D") (pinfunction "8_8D") (pintype "bidirectional"))
    )
    (net (code "60") (name "/LVDSC4_P") (class "Default")
      (node (ref "D2") (pin "6") (pinfunction "I/O4_6") (pintype "bidirectional"))
      (node (ref "J15") (pin "7D") (pinfunction "7_7D") (pintype "bidirectional"))
    )
    (net (code "61") (name "/LVDSC5_N") (class "Default")
      (node (ref "D3") (pin "1") (pinfunction "I/O1_1") (pintype "bidirectional"))
      (node (ref "J15") (pin "2C") (pinfunction "2_2C") (pintype "bidirectional"))
    )
    (net (code "62") (name "/LVDSC5_P") (class "Default")
      (node (ref "D3") (pin "3") (pinfunction "I/O2_3") (pintype "bidirectional"))
      (node (ref "J15") (pin "1C") (pinfunction "1_1C") (pintype "bidirectional"))
    )
    (net (code "63") (name "/LVDSC6_N") (class "Default")
      (node (ref "D4") (pin "1") (pinfunction "I/O1_1") (pintype "bidirectional"))
      (node (ref "J15") (pin "5C") (pinfunction "5_5C") (pintype "bidirectional"))
    )
    (net (code "64") (name "/LVDSC6_P") (class "Default")
      (node (ref "D4") (pin "3") (pinfunction "I/O2_3") (pintype "bidirectional"))
      (node (ref "J15") (pin "4C") (pinfunction "4_4C") (pintype "bidirectional"))
    )
    (net (code "65") (name "/LVDSC7_N") (class "Default")
      (node (ref "D3") (pin "4") (pinfunction "I/O3_4") (pintype "bidirectional"))
      (node (ref "J15") (pin "6C") (pinfunction "6_6C") (pintype "bidirectional"))
    )
    (net (code "66") (name "/LVDSC7_P") (class "Default")
      (node (ref "D3") (pin "6") (pinfunction "I/O4_6") (pintype "bidirectional"))
      (node (ref "J15") (pin "3C") (pinfunction "3_3C") (pintype "bidirectional"))
    )
    (net (code "67") (name "/LVDSC8_N") (class "Default")
      (node (ref "D4") (pin "4") (pinfunction "I/O3_4") (pintype "bidirectional"))
      (node (ref "J15") (pin "8C") (pinfunction "8_8C") (pintype "bidirectional"))
    )
    (net (code "68") (name "/LVDSC8_P") (class "Default")
      (node (ref "D4") (pin "6") (pinfunction "I/O4_6") (pintype "bidirectional"))
      (node (ref "J15") (pin "7C") (pinfunction "7_7C") (pintype "bidirectional"))
    )
    (net (code "69") (name "/LVDSC9_N") (class "Default")
      (node (ref "D5") (pin "3") (pinfunction "I/O2_3") (pintype "bidirectional"))
      (node (ref "J15") (pin "2B") (pinfunction "2_2B") (pintype "bidirectional"))
    )
    (net (code "70") (name "/LVDSC9_P") (class "Default")
      (node (ref "D5") (pin "1") (pinfunction "I/O1_1") (pintype "bidirectional"))
      (node (ref "J15") (pin "1B") (pinfunction "1_1B") (pintype "bidirectional"))
    )
    (net (code "71") (name "/LVDSC10_N") (class "Default")
      (node (ref "D6") (pin "3") (pinfunction "I/O2_3") (pintype "bidirectional"))
      (node (ref "J15") (pin "5B") (pinfunction "5_5B") (pintype "bidirectional"))
    )
    (net (code "72") (name "/LVDSC10_P") (class "Default")
      (node (ref "D6") (pin "1") (pinfunction "I/O1_1") (pintype "bidirectional"))
      (node (ref "J15") (pin "4B") (pinfunction "4_4B") (pintype "bidirectional"))
    )
    (net (code "73") (name "/LVDSC11_N") (class "Default")
      (node (ref "D5") (pin "4") (pinfunction "I/O3_4") (pintype "bidirectional"))
      (node (ref "J15") (pin "6B") (pinfunction "6_6B") (pintype "bidirectional"))
    )
    (net (code "74") (name "/LVDSC11_P") (class "Default")
      (node (ref "D5") (pin "6") (pinfunction "I/O4_6") (pintype "bidirectional"))
      (node (ref "J15") (pin "3B") (pinfunction "3_3B") (pintype "bidirectional"))
    )
    (net (code "75") (name "/LVDSC12_N") (class "Default")
      (node (ref "D6") (pin "4") (pinfunction "I/O3_4") (pintype "bidirectional"))
      (node (ref "J15") (pin "8B") (pinfunction "8_8B") (pintype "bidirectional"))
    )
    (net (code "76") (name "/LVDSC12_P") (class "Default")
      (node (ref "D6") (pin "6") (pinfunction "I/O4_6") (pintype "bidirectional"))
      (node (ref "J15") (pin "7B") (pinfunction "7_7B") (pintype "bidirectional"))
    )
    (net (code "77") (name "/LVDSC13_N") (class "Default")
      (node (ref "D7") (pin "3") (pinfunction "I/O2_3") (pintype "bidirectional"))
      (node (ref "J15") (pin "2A") (pinfunction "2_2A") (pintype "bidirectional"))
    )
    (net (code "78") (name "/LVDSC13_P") (class "Default")
      (node (ref "D7") (pin "1") (pinfunction "I/O1_1") (pintype "bidirectional"))
      (node (ref "J15") (pin "1A") (pinfunction "1_1A") (pintype "bidirectional"))
    )
    (net (code "79") (name "/LVDSC14_N") (class "Default")
      (node (ref "D8") (pin "3") (pinfunction "I/O2_3") (pintype "bidirectional"))
      (node (ref "J15") (pin "5A") (pinfunction "5_5A") (pintype "bidirectional"))
    )
    (net (code "80") (name "/LVDSC14_P") (class "Default")
      (node (ref "D8") (pin "1") (pinfunction "I/O1_1") (pintype "bidirectional"))
      (node (ref "J15") (pin "4A") (pinfunction "4_4A") (pintype "bidirectional"))
    )
    (net (code "81") (name "/LVDSC15_N") (class "Default")
      (node (ref "D7") (pin "4") (pinfunction "I/O3_4") (pintype "bidirectional"))
      (node (ref "J15") (pin "6A") (pinfunction "6_6A") (pintype "bidirectional"))
    )
    (net (code "82") (name "/LVDSC15_P") (class "Default")
      (node (ref "D7") (pin "6") (pinfunction "I/O4_6") (pintype "bidirectional"))
      (node (ref "J15") (pin "3A") (pinfunction "3_3A") (pintype "bidirectional"))
    )
    (net (code "83") (name "/LVDSC16_N") (class "Default")
      (node (ref "D8") (pin "4") (pinfunction "I/O3_4") (pintype "bidirectional"))
      (node (ref "J15") (pin "8A") (pinfunction "8_8A") (pintype "bidirectional"))
    )
    (net (code "84") (name "/LVDSC16_P") (class "Default")
      (node (ref "D8") (pin "6") (pinfunction "I/O4_6") (pintype "bidirectional"))
      (node (ref "J15") (pin "7A") (pinfunction "7_7A") (pintype "bidirectional"))
    )
    (net (code "85") (name "GND") (class "Default")
      (node (ref "B5") (pin "1") (pinfunction "1_1") (pintype "bidirectional"))
      (node (ref "B7") (pin "1") (pinfunction "1_1") (pintype "bidirectional"))
      (node (ref "B9") (pin "1") (pinfunction "1_1") (pintype "bidirectional"))
      (node (ref "C57") (pin "1") (pinfunction "1_1") (pintype "passive"))
      (node (ref "C58") (pin "1") (pinfunction "1_1") (pintype "passive"))
      (node (ref "C59") (pin "1") (pinfunction "1_1") (pintype "passive"))
      (node (ref "C60") (pin "1") (pinfunction "1_1") (pintype "passive"))
      (node (ref "C61") (pin "1") (pinfunction "1_1") (pintype "passive"))
      (node (ref "C62") (pin "2") (pinfunction "2_2") (pintype "passive"))
      (node (ref "C63") (pin "1") (pinfunction "1_1") (pintype "passive"))
      (node (ref "C64") (pin "1") (pinfunction "1_1") (pintype "passive"))
      (node (ref "C65") (pin "1") (pinfunction "1_1") (pintype "passive"))
      (node (ref "C66") (pin "1") (pinfunction "1_1") (pintype "passive"))
      (node (ref "C67") (pin "1") (pinfunction "1_1") (pintype "passive"))
      (node (ref "C68") (pin "1") (pinfunction "1_1") (pintype "passive"))
      (node (ref "D1") (pin "2") (pinfunction "GND_2") (pintype "power_in"))
      (node (ref "D2") (pin "2") (pinfunction "GND_2") (pintype "power_in"))
      (node (ref "D3") (pin "2") (pinfunction "GND_2") (pintype "power_in"))
      (node (ref "D4") (pin "2") (pinfunction "GND_2") (pintype "power_in"))
      (node (ref "D5") (pin "2") (pinfunction "GND_2") (pintype "power_in"))
      (node (ref "D6") (pin "2") (pinfunction "GND_2") (pintype "power_in"))
      (node (ref "D7") (pin "2") (pinfunction "GND_2") (pintype "power_in"))
      (node (ref "D8") (pin "2") (pinfunction "GND_2") (pintype "power_in"))
      (node (ref "IC23") (pin "1") (pinfunction "A0_1") (pintype "input"))
      (node (ref "IC23") (pin "8") (pinfunction "GND_8") (pintype "power_in"))
      (node (ref "IC24") (pin "2") (pinfunction "VSS_2") (pintype "power_in"))
      (node (ref "IC25") (pin "1") (pinfunction "A0_1") (pintype "input"))
      (node (ref "IC25") (pin "8") (pinfunction "GND_8") (pintype "power_in"))
      (node (ref "IC26") (pin "2") (pinfunction "VSS_2") (pintype "power_in"))
      (node (ref "IC27") (pin "1") (pinfunction "PGND_1") (pintype "power_in"))
      (node (ref "IC27") (pin "11") (pinfunction "EP_11") (pintype "power_in"))
      (node (ref "IC27") (pin "6") (pinfunction "AGND_6") (pintype "power_in"))
      (node (ref "J14") (pin "1") (pinfunction "1_1") (pintype "bidirectional"))
      (node (ref "J14") (pin "10") (pinfunction "10_10") (pintype "bidirectional"))
      (node (ref "J14") (pin "13") (pinfunction "13_13") (pintype "bidirectional"))
      (node (ref "J14") (pin "16") (pinfunction "16_16") (pintype "bidirectional"))
      (node (ref "J14") (pin "19") (pinfunction "19_19") (pintype "bidirectional"))
      (node (ref "J14") (pin "22") (pinfunction "22_22") (pintype "bidirectional"))
      (node (ref "J14") (pin "25") (pinfunction "25_25") (pintype "bidirectional"))
      (node (ref "J14") (pin "4") (pinfunction "4_4") (pintype "bidirectional"))
      (node (ref "J14") (pin "7") (pinfunction "7_7") (pintype "bidirectional"))
      (node (ref "J15") (pin "SH") (pinfunction "1_SH") (pintype "passive"))
      (node (ref "J24") (pin "1") (pinfunction "1_1") (pintype "bidirectional"))
      (node (ref "J24") (pin "10") (pinfunction "10_10") (pintype "bidirectional"))
      (node (ref "J24") (pin "13") (pinfunction "13_13") (pintype "bidirectional"))
      (node (ref "J24") (pin "16") (pinfunction "16_16") (pintype "bidirectional"))
      (node (ref "J24") (pin "19") (pinfunction "19_19") (pintype "bidirectional"))
      (node (ref "J24") (pin "22") (pinfunction "22_22") (pintype "bidirectional"))
      (node (ref "J24") (pin "25") (pinfunction "25_25") (pintype "bidirectional"))
      (node (ref "J24") (pin "4") (pinfunction "4_4") (pintype "bidirectional"))
      (node (ref "J24") (pin "7") (pinfunction "7_7") (pintype "bidirectional"))
      (node (ref "LD5") (pin "1") (pinfunction "C_1") (pintype "passive"))
      (node (ref "LD6") (pin "1") (pinfunction "C_1") (pintype "passive"))
      (node (ref "LD7") (pin "1") (pinfunction "C_1") (pintype "passive"))
      (node (ref "LD8") (pin "1") (pinfunction "C_1") (pintype "passive"))
      (node (ref "R122") (pin "1") (pinfunction "1_1") (pintype "passive"))
      (node (ref "SW5") (pin "10") (pinfunction "10_10") (pintype "passive"))
      (node (ref "SW5") (pin "11") (pinfunction "11_11") (pintype "passive"))
      (node (ref "SW5") (pin "12") (pinfunction "12_12") (pintype "passive"))
      (node (ref "SW5") (pin "13") (pinfunction "13_13") (pintype "passive"))
      (node (ref "SW5") (pin "14") (pinfunction "14_14") (pintype "passive"))
      (node (ref "SW5") (pin "15") (pinfunction "15_15") (pintype "passive"))
      (node (ref "SW5") (pin "16") (pinfunction "16_16") (pintype "passive"))
      (node (ref "SW5") (pin "9") (pinfunction "9_9") (pintype "passive"))
      (node (ref "SW6") (pin "10") (pinfunction "10_10") (pintype "passive"))
      (node (ref "SW6") (pin "11") (pinfunction "11_11") (pintype "passive"))
      (node (ref "SW6") (pin "12") (pinfunction "12_12") (pintype "passive"))
      (node (ref "SW6") (pin "13") (pinfunction "13_13") (pintype "passive"))
      (node (ref "SW6") (pin "14") (pinfunction "14_14") (pintype "passive"))
      (node (ref "SW6") (pin "15") (pinfunction "15_15") (pintype "passive"))
      (node (ref "SW6") (pin "16") (pinfunction "16_16") (pintype "passive"))
      (node (ref "SW6") (pin "9") (pinfunction "9_9") (pintype "passive"))
    )
    (net (code "86") (name "Net-(IC27-FB)") (class "Default")
      (node (ref "IC27") (pin "5") (pinfunction "FB_5") (pintype "input"))
      (node (ref "R121") (pin "1") (pinfunction "1_1") (pintype "passive"))
      (node (ref "R122") (pin "2") (pinfunction "2_2") (pintype "passive"))
    )
    (net (code "87") (name "Net-(IC27-SW)") (class "Default")
      (node (ref "IC27") (pin "9") (pinfunction "SW_9") (pintype "output"))
      (node (ref "L2") (pin "1") (pinfunction "1_1") (pintype "passive"))
    )
    (net (code "88") (name "Net-(LD1A-C)") (class "Default")
      (node (ref "LD1") (pin "1") (pinfunction "C_1") (pintype "passive"))
      (node (ref "R89") (pin "1") (pinfunction "1_1") (pintype "passive"))
    )
    (net (code "89") (name "Net-(LD1B-C)") (class "Default")
      (node (ref "LD1") (pin "3") (pinfunction "C_3") (pintype "passive"))
      (node (ref "R91") (pin "1") (pinfunction "1_1") (pintype "passive"))
    )
    (net (code "90") (name "Net-(LD1C-C)") (class "Default")
      (node (ref "LD1") (pin "5") (pinfunction "C_5") (pintype "passive"))
      (node (ref "R93") (pin "1") (pinfunction "1_1") (pintype "passive"))
    )
    (net (code "91") (name "Net-(LD1D-C)") (class "Default")
      (node (ref "LD1") (pin "7") (pinfunction "C_7") (pintype "passive"))
      (node (ref "R95") (pin "1") (pinfunction "1_1") (pintype "passive"))
    )
    (net (code "92") (name "Net-(LD2A-C)") (class "Default")
      (node (ref "LD2") (pin "1") (pinfunction "C_1") (pintype "passive"))
      (node (ref "R97") (pin "1") (pinfunction "1_1") (pintype "passive"))
    )
    (net (code "93") (name "Net-(LD2B-C)") (class "Default")
      (node (ref "LD2") (pin "3") (pinfunction "C_3") (pintype "passive"))
      (node (ref "R99") (pin "1") (pinfunction "1_1") (pintype "passive"))
    )
    (net (code "94") (name "Net-(LD2C-C)") (class "Default")
      (node (ref "LD2") (pin "5") (pinfunction "C_5") (pintype "passive"))
      (node (ref "R101") (pin "1") (pinfunction "1_1") (pintype "passive"))
    )
    (net (code "95") (name "Net-(LD2D-C)") (class "Default")
      (node (ref "LD2") (pin "7") (pinfunction "C_7") (pintype "passive"))
      (node (ref "R103") (pin "1") (pinfunction "1_1") (pintype "passive"))
    )
    (net (code "96") (name "Net-(LD3A-C)") (class "Default")
      (node (ref "LD3") (pin "1") (pinfunction "C_1") (pintype "passive"))
      (node (ref "R105") (pin "1") (pinfunction "1_1") (pintype "passive"))
    )
    (net (code "97") (name "Net-(LD3B-C)") (class "Default")
      (node (ref "LD3") (pin "3") (pinfunction "C_3") (pintype "passive"))
      (node (ref "R107") (pin "1") (pinfunction "1_1") (pintype "passive"))
    )
    (net (code "98") (name "Net-(LD3C-C)") (class "Default")
      (node (ref "LD3") (pin "5") (pinfunction "C_5") (pintype "passive"))
      (node (ref "R109") (pin "1") (pinfunction "1_1") (pintype "passive"))
    )
    (net (code "99") (name "Net-(LD3D-C)") (class "Default")
      (node (ref "LD3") (pin "7") (pinfunction "C_7") (pintype "passive"))
      (node (ref "R111") (pin "1") (pinfunction "1_1") (pintype "passive"))
    )
    (net (code "100") (name "Net-(LD4A-C)") (class "Default")
      (node (ref "LD4") (pin "1") (pinfunction "C_1") (pintype "passive"))
      (node (ref "R113") (pin "1") (pinfunction "1_1") (pintype "passive"))
    )
    (net (code "101") (name "Net-(LD4B-C)") (class "Default")
      (node (ref "LD4") (pin "3") (pinfunction "C_3") (pintype "passive"))
      (node (ref "R115") (pin "1") (pinfunction "1_1") (pintype "passive"))
    )
    (net (code "102") (name "Net-(LD4C-C)") (class "Default")
      (node (ref "LD4") (pin "5") (pinfunction "C_5") (pintype "passive"))
      (node (ref "R117") (pin "1") (pinfunction "1_1") (pintype "passive"))
    )
    (net (code "103") (name "Net-(LD4D-C)") (class "Default")
      (node (ref "LD4") (pin "7") (pinfunction "C_7") (pintype "passive"))
      (node (ref "R119") (pin "1") (pinfunction "1_1") (pintype "passive"))
    )
    (net (code "104") (name "Net-(LD5-A)") (class "Default")
      (node (ref "LD5") (pin "2") (pinfunction "A_2") (pintype "passive"))
      (node (ref "R1") (pin "1") (pinfunction "1_1") (pintype "passive"))
    )
    (net (code "105") (name "Net-(LD6-A)") (class "Default")
      (node (ref "LD6") (pin "2") (pinfunction "A_2") (pintype "passive"))
      (node (ref "R3") (pin "2") (pinfunction "2_2") (pintype "passive"))
    )
    (net (code "106") (name "Net-(LD7-A)") (class "Default")
      (node (ref "LD7") (pin "2") (pinfunction "A_2") (pintype "passive"))
      (node (ref "R5") (pin "2") (pinfunction "2_2") (pintype "passive"))
    )
    (net (code "107") (name "Net-(LD8-A)") (class "Default")
      (node (ref "LD8") (pin "2") (pinfunction "A_2") (pintype "passive"))
      (node (ref "R7") (pin "2") (pinfunction "2_2") (pintype "passive"))
    )
    (net (code "108") (name "Net-(R2-Pad2)") (class "Default")
      (node (ref "R2") (pin "2") (pinfunction "2_2") (pintype "passive"))
      (node (ref "R3") (pin "1") (pinfunction "1_1") (pintype "passive"))
    )
    (net (code "109") (name "Net-(R4-Pad2)") (class "Default")
      (node (ref "R4") (pin "2") (pinfunction "2_2") (pintype "passive"))
      (node (ref "R5") (pin "1") (pinfunction "1_1") (pintype "passive"))
    )
    (net (code "110") (name "Net-(R6-Pad2)") (class "Default")
      (node (ref "R6") (pin "2") (pinfunction "2_2") (pintype "passive"))
      (node (ref "R7") (pin "1") (pinfunction "1_1") (pintype "passive"))
    )
    (net (code "111") (name "P3V3") (class "Default")
      (node (ref "B10") (pin "1") (pinfunction "1_1") (pintype "bidirectional"))
      (node (ref "C59") (pin "2") (pinfunction "2_2") (pintype "passive"))
      (node (ref "C60") (pin "2") (pinfunction "2_2") (pintype "passive"))
      (node (ref "C61") (pin "2") (pinfunction "2_2") (pintype "passive"))
      (node (ref "C62") (pin "1") (pinfunction "1_1") (pintype "passive"))
      (node (ref "C65") (pin "2") (pinfunction "2_2") (pintype "passive"))
      (node (ref "C66") (pin "2") (pinfunction "2_2") (pintype "passive"))
      (node (ref "D1") (pin "5") (pinfunction "VBUS_5") (pintype "power_in"))
      (node (ref "D2") (pin "5") (pinfunction "VBUS_5") (pintype "power_in"))
      (node (ref "D3") (pin "5") (pinfunction "VBUS_5") (pintype "power_in"))
      (node (ref "D4") (pin "5") (pinfunction "VBUS_5") (pintype "power_in"))
      (node (ref "D5") (pin "5") (pinfunction "VBUS_5") (pintype "power_in"))
      (node (ref "D6") (pin "5") (pinfunction "VBUS_5") (pintype "power_in"))
      (node (ref "D7") (pin "5") (pinfunction "VBUS_5") (pintype "power_in"))
      (node (ref "D8") (pin "5") (pinfunction "VBUS_5") (pintype "power_in"))
      (node (ref "IC27") (pin "10") (pinfunction "VOS_10") (pintype "input"))
      (node (ref "IC27") (pin "8") (pinfunction "SLEEP_8") (pintype "input"))
      (node (ref "L2") (pin "2") (pinfunction "2_2") (pintype "passive"))
      (node (ref "LD1") (pin "2") (pinfunction "A_2") (pintype "passive"))
      (node (ref "LD1") (pin "4") (pinfunction "A_4") (pintype "passive"))
      (node (ref "LD1") (pin "6") (pinfunction "A_6") (pintype "passive"))
      (node (ref "LD1") (pin "8") (pinfunction "A_8") (pintype "passive"))
      (node (ref "LD2") (pin "2") (pinfunction "A_2") (pintype "passive"))
      (node (ref "LD2") (pin "4") (pinfunction "A_4") (pintype "passive"))
      (node (ref "LD2") (pin "6") (pinfunction "A_6") (pintype "passive"))
      (node (ref "LD2") (pin "8") (pinfunction "A_8") (pintype "passive"))
      (node (ref "LD3") (pin "2") (pinfunction "A_2") (pintype "passive"))
      (node (ref "LD3") (pin "4") (pinfunction "A_4") (pintype "passive"))
      (node (ref "LD3") (pin "6") (pinfunction "A_6") (pintype "passive"))
      (node (ref "LD3") (pin "8") (pinfunction "A_8") (pintype "passive"))
      (node (ref "LD4") (pin "2") (pinfunction "A_2") (pintype "passive"))
      (node (ref "LD4") (pin "4") (pinfunction "A_4") (pintype "passive"))
      (node (ref "LD4") (pin "6") (pinfunction "A_6") (pintype "passive"))
      (node (ref "LD4") (pin "8") (pinfunction "A_8") (pintype "passive"))
      (node (ref "R100") (pin "2") (pinfunction "2_2") (pintype "passive"))
      (node (ref "R102") (pin "2") (pinfunction "2_2") (pintype "passive"))
      (node (ref "R104") (pin "2") (pinfunction "2_2") (pintype "passive"))
      (node (ref "R106") (pin "2") (pinfunction "2_2") (pintype "passive"))
      (node (ref "R108") (pin "2") (pinfunction "2_2") (pintype "passive"))
      (node (ref "R110") (pin "2") (pinfunction "2_2") (pintype "passive"))
      (node (ref "R112") (pin "2") (pinfunction "2_2") (pintype "passive"))
      (node (ref "R114") (pin "2") (pinfunction "2_2") (pintype "passive"))
      (node (ref "R116") (pin "2") (pinfunction "2_2") (pintype "passive"))
      (node (ref "R118") (pin "2") (pinfunction "2_2") (pintype "passive"))
      (node (ref "R120") (pin "2") (pinfunction "2_2") (pintype "passive"))
      (node (ref "R121") (pin "2") (pinfunction "2_2") (pintype "passive"))
      (node (ref "R2") (pin "1") (pinfunction "1_1") (pintype "passive"))
      (node (ref "R90") (pin "2") (pinfunction "2_2") (pintype "passive"))
      (node (ref "R92") (pin "2") (pinfunction "2_2") (pintype "passive"))
      (node (ref "R94") (pin "2") (pinfunction "2_2") (pintype "passive"))
      (node (ref "R96") (pin "2") (pinfunction "2_2") (pintype "passive"))
      (node (ref "R98") (pin "2") (pinfunction "2_2") (pintype "passive"))
    )
    (net (code "112") (name "P3V3_MP1") (class "Default")
      (node (ref "B8") (pin "1") (pinfunction "1_1") (pintype "bidirectional"))
      (node (ref "C57") (pin "2") (pinfunction "2_2") (pintype "passive"))
      (node (ref "C58") (pin "2") (pinfunction "2_2") (pintype "passive"))
      (node (ref "IC23") (pin "16") (pinfunction "VCC_16") (pintype "bidirectional"))
      (node (ref "IC23") (pin "2") (pinfunction "A1_2") (pintype "input"))
      (node (ref "IC23") (pin "3") (pinfunction "A2_3") (pintype "input"))
      (node (ref "IC24") (pin "4") (pinfunction "VCC_4") (pintype "power_in"))
      (node (ref "J14") (pin "30") (pinfunction "30_30") (pintype "bidirectional"))
      (node (ref "R6") (pin "1") (pinfunction "1_1") (pintype "passive"))
    )
    (net (code "113") (name "P3V3_MP2") (class "Default")
      (node (ref "B6") (pin "1") (pinfunction "1_1") (pintype "bidirectional"))
      (node (ref "C63") (pin "2") (pinfunction "2_2") (pintype "passive"))
      (node (ref "C64") (pin "2") (pinfunction "2_2") (pintype "passive"))
      (node (ref "IC25") (pin "16") (pinfunction "VCC_16") (pintype "bidirectional"))
      (node (ref "IC25") (pin "2") (pinfunction "A1_2") (pintype "input"))
      (node (ref "IC25") (pin "3") (pinfunction "A2_3") (pintype "input"))
      (node (ref "IC26") (pin "4") (pinfunction "VCC_4") (pintype "power_in"))
      (node (ref "J24") (pin "30") (pinfunction "30_30") (pintype "bidirectional"))
      (node (ref "R4") (pin "1") (pinfunction "1_1") (pintype "passive"))
    )
    (net (code "114") (name "P12V0") (class "Default")
      (node (ref "B11") (pin "1") (pinfunction "1_1") (pintype "bidirectional"))
      (node (ref "C67") (pin "2") (pinfunction "2_2") (pintype "passive"))
      (node (ref "C68") (pin "2") (pinfunction "2_2") (pintype "passive"))
      (node (ref "IC27") (pin "2") (pinfunction "VIN_2") (pintype "input"))
      (node (ref "IC27") (pin "3") (pinfunction "EN_3") (pintype "input"))
      (node (ref "J14") (pin "28") (pinfunction "28_28") (pintype "bidirectional"))
      (node (ref "J14") (pin "29") (pinfunction "29_29") (pintype "bidirectional"))
      (node (ref "J24") (pin "28") (pinfunction "28_28") (pintype "bidirectional"))
      (node (ref "J24") (pin "29") (pinfunction "29_29") (pintype "bidirectional"))
      (node (ref "R1") (pin "2") (pinfunction "2_2") (pintype "passive"))
    )
    (net (code "115") (name "unconnected-(IC23-~{INT}-Pad13)") (class "Default")
      (node (ref "IC23") (pin "13") (pinfunction "~{INT}_13") (pintype "output"))
    )
    (net (code "116") (name "unconnected-(IC24-NC-Pad5)") (class "Default")
      (node (ref "IC24") (pin "5") (pinfunction "NC_5") (pintype "passive"))
    )
    (net (code "117") (name "unconnected-(IC25-~{INT}-Pad13)") (class "Default")
      (node (ref "IC25") (pin "13") (pinfunction "~{INT}_13") (pintype "output"))
    )
    (net (code "118") (name "unconnected-(IC26-NC-Pad5)") (class "Default")
      (node (ref "IC26") (pin "5") (pinfunction "NC_5") (pintype "passive"))
    )
    (net (code "119") (name "unconnected-(IC27-NC-Pad4)") (class "Default")
      (node (ref "IC27") (pin "4") (pinfunction "NC_4") (pintype "passive"))
    )
    (net (code "120") (name "unconnected-(IC27-PG-Pad7)") (class "Default")
      (node (ref "IC27") (pin "7") (pinfunction "PG_7") (pintype "output"))
    )
  )
)
